# bqZUM_Bluetooth.net
KiCad netlist of a schematic drawn in Altium Designer
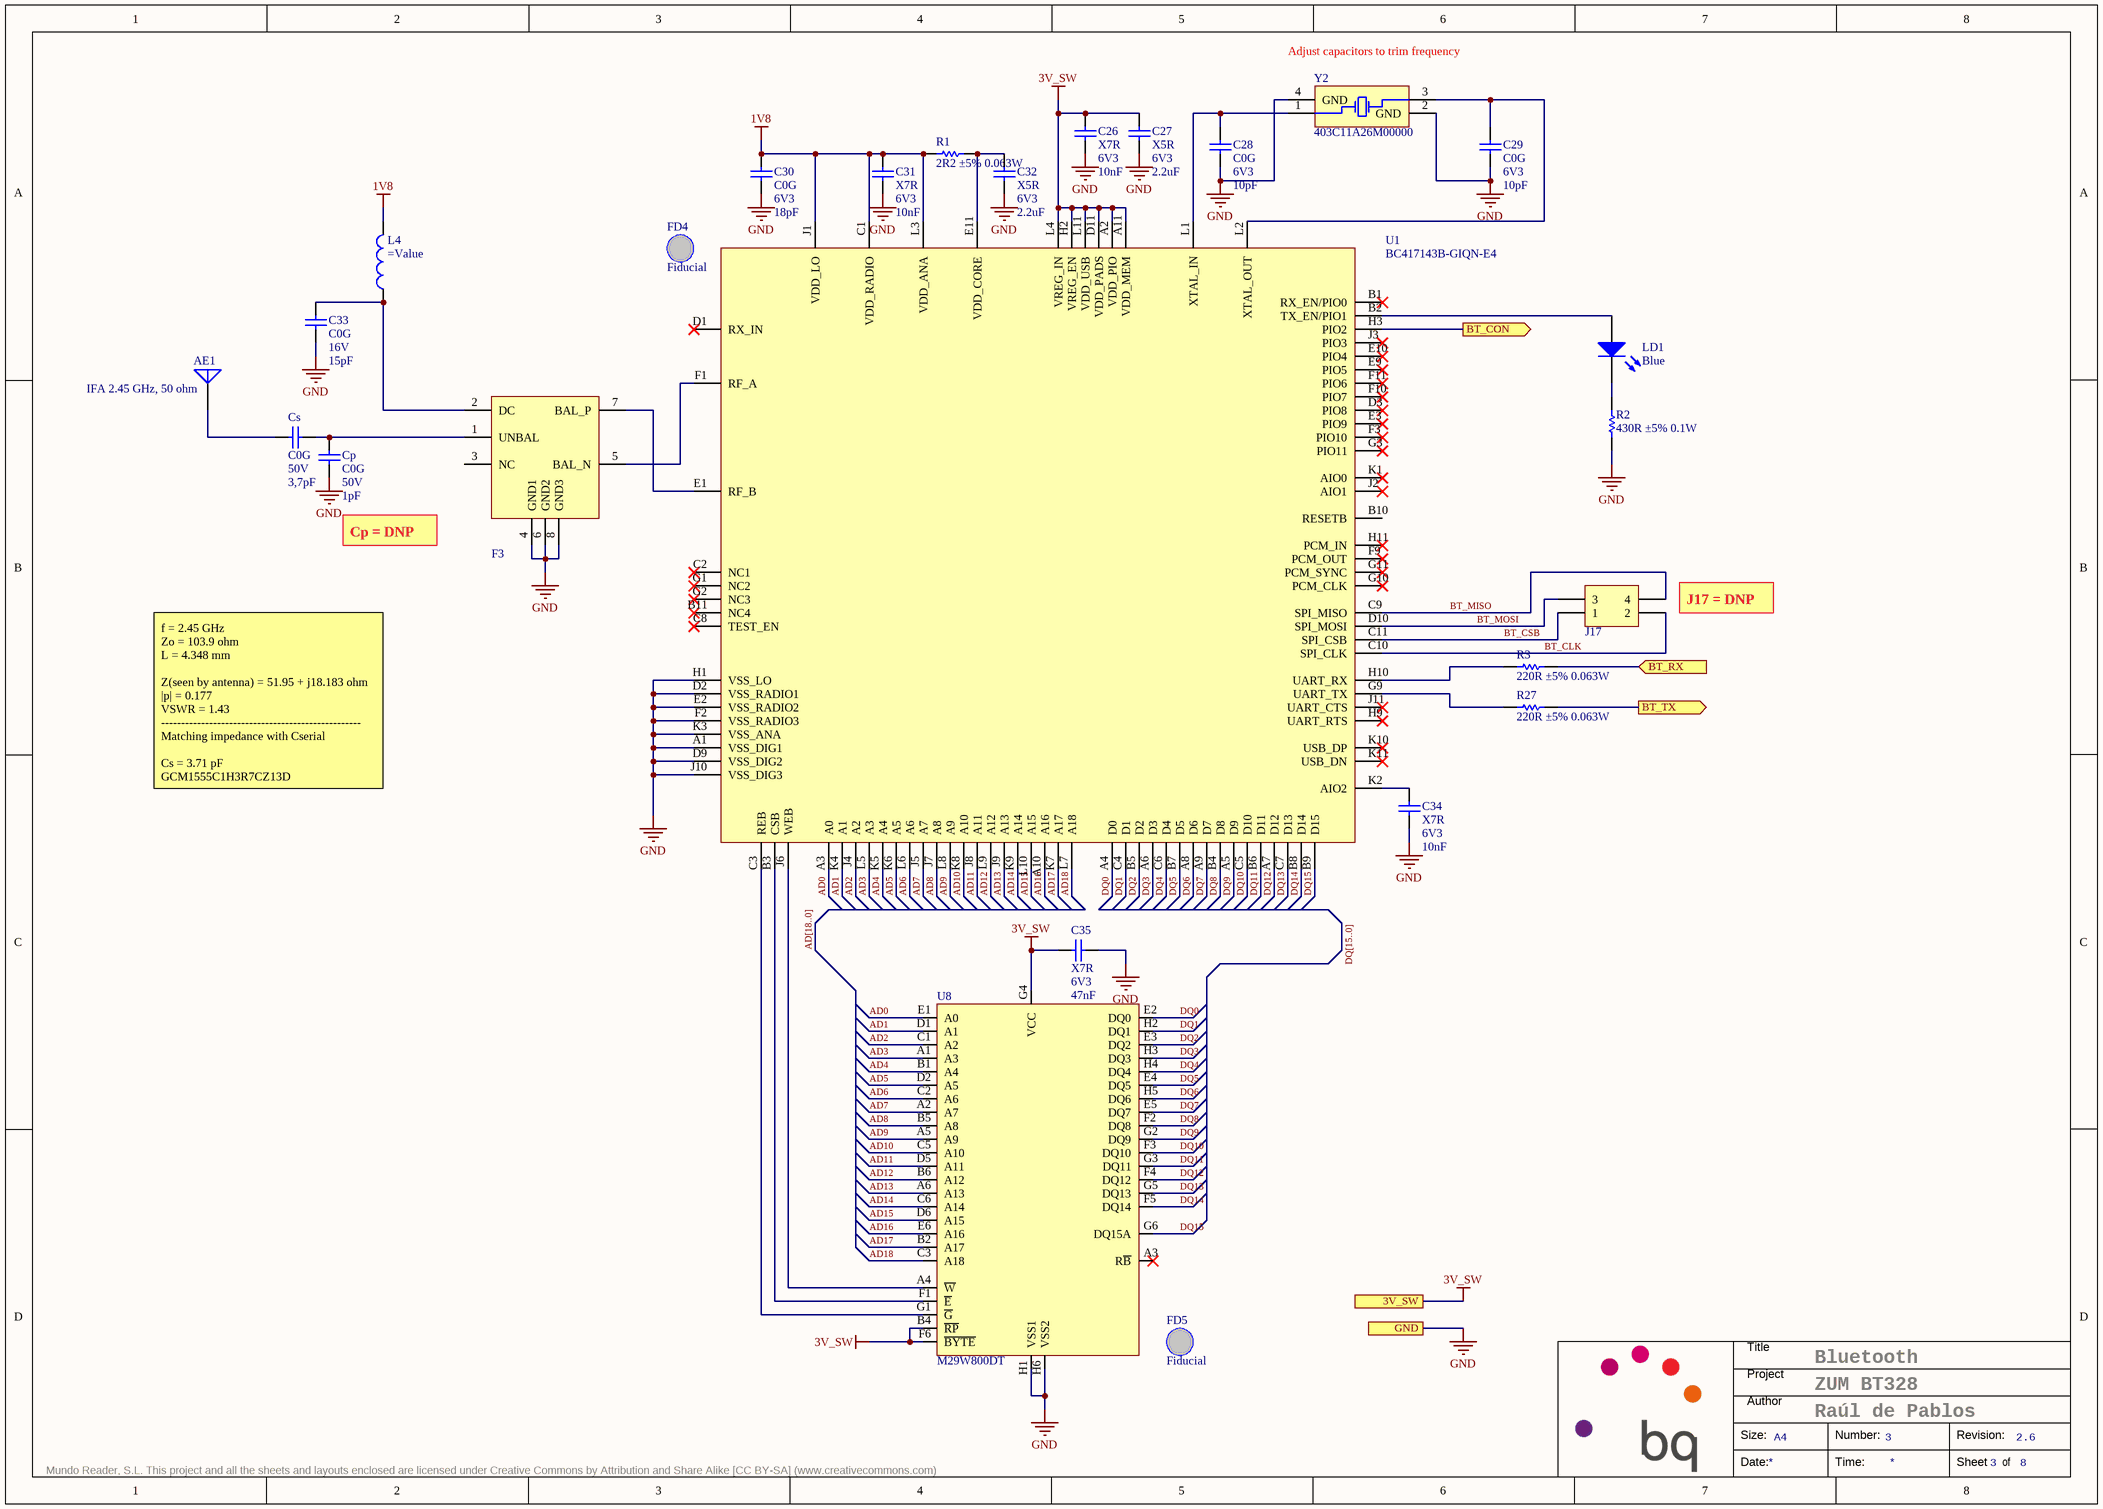
[diagram p0: bqZUM_Bluetooth.SchDoc]

(export (version "E")
  (design (tool "Eeschema 10.0.6"))
  (components
    (comp (ref "AE1")
      (value "~")
      (footprint "IFA_2,45GHZ_50OHM")
      (description "Antenna with Ground")
      (fields (field (name "PART NUMBER") "Microstrip_2.4GHz"))
      (libsource (lib "Connectors_Antenna") (part "Antenna_WG"))
    )
    (comp (ref "C26")
      (value "Capacitor")
      (footprint "C0402")
      (fields
        (field (name "DIELECTRIC") "X7R")
        (field (name "VOLTAGE") "6V3")
        (field (name "CAPACITANCE") "10nF")
        (field (name "PART NUMBER") "C0402_10nF_6V3_±10%")
        (field (name "TOLERANCE") "±10%")
        (field (name "MANUFACTURER") "Kemet")
      )
      (libsource (lib "Pasives_Capacitor_SMD") (part "Capacitor"))
    )
    (comp (ref "C27")
      (value "Capacitor")
      (footprint "C0603")
      (fields
        (field (name "DIELECTRIC") "X5R")
        (field (name "VOLTAGE") "6V3")
        (field (name "CAPACITANCE") "2.2uF")
        (field (name "PART NUMBER") "C0603_2.2uF_6V3_±10%")
        (field (name "TOLERANCE") "±10%")
        (field (name "MANUFACTURER") "Kemet")
      )
      (libsource (lib "Pasives_Capacitor_SMD") (part "Capacitor"))
    )
    (comp (ref "C28")
      (value "Capacitor")
      (footprint "C0402")
      (fields
        (field (name "DIELECTRIC") "C0G")
        (field (name "VOLTAGE") "6V3")
        (field (name "CAPACITANCE") "10pF")
        (field (name "PART NUMBER") "C0402_10pF_6V3_±10%")
        (field (name "TOLERANCE") "±10%")
        (field (name "MANUFACTURER") "Kemet")
      )
      (libsource (lib "Pasives_Capacitor_SMD") (part "Capacitor"))
    )
    (comp (ref "C29")
      (value "Capacitor")
      (footprint "C0402")
      (fields
        (field (name "DIELECTRIC") "C0G")
        (field (name "VOLTAGE") "6V3")
        (field (name "CAPACITANCE") "10pF")
        (field (name "PART NUMBER") "C0402_10pF_6V3_±10%")
        (field (name "TOLERANCE") "±10%")
        (field (name "MANUFACTURER") "Kemet")
      )
      (libsource (lib "Pasives_Capacitor_SMD") (part "Capacitor"))
    )
    (comp (ref "C30")
      (value "Capacitor")
      (footprint "C0402")
      (fields
        (field (name "DIELECTRIC") "C0G")
        (field (name "VOLTAGE") "6V3")
        (field (name "CAPACITANCE") "18pF")
        (field (name "PART NUMBER") "C0402_18pF_6V3_±10%")
        (field (name "TOLERANCE") "±10%")
        (field (name "MANUFACTURER") "Kemet")
      )
      (libsource (lib "Pasives_Capacitor_SMD") (part "Capacitor"))
    )
    (comp (ref "C31")
      (value "Capacitor")
      (footprint "C0402")
      (fields
        (field (name "DIELECTRIC") "X7R")
        (field (name "VOLTAGE") "6V3")
        (field (name "CAPACITANCE") "10nF")
        (field (name "PART NUMBER") "C0402_10nF_6V3_±10%")
        (field (name "TOLERANCE") "±10%")
        (field (name "MANUFACTURER") "Kemet")
      )
      (libsource (lib "Pasives_Capacitor_SMD") (part "Capacitor"))
    )
    (comp (ref "C32")
      (value "Capacitor")
      (footprint "C0603")
      (fields
        (field (name "DIELECTRIC") "X5R")
        (field (name "VOLTAGE") "6V3")
        (field (name "CAPACITANCE") "2.2uF")
        (field (name "PART NUMBER") "C0603_2.2uF_6V3_±10%")
        (field (name "TOLERANCE") "±10%")
        (field (name "MANUFACTURER") "Kemet")
      )
      (libsource (lib "Pasives_Capacitor_SMD") (part "Capacitor"))
    )
    (comp (ref "C33")
      (value "Capacitor")
      (footprint "C0402")
      (fields
        (field (name "DIELECTRIC") "C0G")
        (field (name "VOLTAGE") "16V")
        (field (name "CAPACITANCE") "15pF")
        (field (name "PART NUMBER") "C0402_15pF_16V_±10%")
        (field (name "TOLERANCE") "±10%")
        (field (name "MANUFACTURER") "Kemet")
      )
      (libsource (lib "Pasives_Capacitor_SMD") (part "Capacitor"))
    )
    (comp (ref "C34")
      (value "Capacitor")
      (footprint "C0402")
      (fields
        (field (name "DIELECTRIC") "X7R")
        (field (name "VOLTAGE") "6V3")
        (field (name "CAPACITANCE") "10nF")
        (field (name "PART NUMBER") "C0402_10nF_6V3_±10%")
        (field (name "TOLERANCE") "±10%")
        (field (name "MANUFACTURER") "Kemet")
      )
      (libsource (lib "Pasives_Capacitor_SMD") (part "Capacitor"))
    )
    (comp (ref "C35")
      (value "Capacitor")
      (footprint "C0402")
      (fields
        (field (name "DIELECTRIC") "X7R")
        (field (name "VOLTAGE") "6V3")
        (field (name "CAPACITANCE") "47nF")
        (field (name "PART NUMBER") "C0402_47nF_6V3_±10%")
        (field (name "TOLERANCE") "±10%")
        (field (name "MANUFACTURER") "Kemet")
      )
      (libsource (lib "Pasives_Capacitor_SMD") (part "Capacitor"))
    )
    (comp (ref "Cp")
      (value "Capacitor")
      (footprint "C0402")
      (fields
        (field (name "DIELECTRIC") "C0G")
        (field (name "VOLTAGE") "50V")
        (field (name "CAPACITANCE") "1pF")
        (field (name "PART NUMBER") "C0402_1pF_50V_0.25pF")
        (field (name "TOLERANCE") "0.25pF")
        (field (name "MANUFACTURER") "Murata")
      )
      (libsource (lib "Pasives_Capacitor_SMD") (part "Capacitor"))
    )
    (comp (ref "Cs")
      (value "Capacitor")
      (footprint "C0402")
      (fields
        (field (name "DIELECTRIC") "C0G")
        (field (name "VOLTAGE") "50V")
        (field (name "CAPACITANCE") "3,7pF")
        (field (name "PART NUMBER") "C0402_3,7pF_50V_±7%")
        (field (name "TOLERANCE") "±7%")
        (field (name "MANUFACTURER") "Murata")
      )
      (libsource (lib "Pasives_Capacitor_SMD") (part "Capacitor"))
    )
    (comp (ref "F3")
      (value "BP_Filter_Balun")
      (footprint "2450FB15K0005")
      (description "Band Pass Balun Filter")
      (fields (field (name "MANUFACTURER") "Johanson Technlogy"))
      (libsource (lib "Pasives_Filter") (part "BP_Filter_Balun"))
    )
    (comp (ref "FD4")
      (value "Fiducial")
      (footprint "Fiducial_Local_0.4mm")
      (fields (field (name "PART NUMBER") "Fiducial Local 0.4mm"))
      (libsource (lib "Miscelanea") (part "Fiducial"))
    )
    (comp (ref "FD5")
      (value "Fiducial")
      (footprint "Fiducial_Local_0.4mm")
      (fields (field (name "PART NUMBER") "Fiducial Local 0.4mm"))
      (libsource (lib "Miscelanea") (part "Fiducial"))
    )
    (comp (ref "J17")
      (value "2x2 Header 1.27mm")
      (footprint "2x2 Header THT 1.27mm")
      (description "4 pin Dual Header 1.27mm")
      (fields (field (name "MANUFACTURER") "Würth") (field (name "PART NUMBER") "CON_DPH_THT_1.27_4"))
      (libsource (lib "Conectores_PinHeader_1.27") (part "2x2 Header 1.27mm"))
    )
    (comp (ref "L4")
      (value "~")
      (footprint "L0402")
      (description "Inductor SMD")
      (fields (field (name "PART NUMBER") "15nH_0,3A") (field (name "MANUFACTURER") "Murata"))
      (libsource (lib "Pasivos_Inductor_SMD") (part "Inductor"))
    )
    (comp (ref "LD1")
      (value "Blue")
      (footprint "LED0603")
      (description "Light Emitting Diode")
      (fields (field (name "PART NUMBER") "LTST-C194TBKT") (field (name "MANUFACTURER") "Lite-On"))
      (libsource (lib "Optoelectronics") (part "LED"))
    )
    (comp (ref "R1")
      (value "2R2 ±5% 0.063W")
      (footprint "R0402")
      (description "Resistor")
      (fields (field (name "TOLERANCE") "±5%") (field (name "POWER") "0.063W"))
      (libsource (lib "Pasives_Resistor_SMD") (part "Resistor"))
    )
    (comp (ref "R2")
      (value "430R ±5% 0.1W")
      (footprint "R0603")
      (description "Resistor")
      (fields (field (name "TOLERANCE") "±5%") (field (name "POWER") "0.1W"))
      (libsource (lib "Pasives_Resistor_SMD") (part "Resistor"))
    )
    (comp (ref "R3")
      (value "220R ±5% 0.063W")
      (footprint "R0402")
      (description "Resistor")
      (fields (field (name "TOLERANCE") "±5%") (field (name "POWER") "0.063W"))
      (libsource (lib "Pasives_Resistor_SMD") (part "Resistor"))
    )
    (comp (ref "R27")
      (value "220R ±5% 0.063W")
      (footprint "R0402")
      (description "Resistor")
      (fields (field (name "TOLERANCE") "±5%") (field (name "POWER") "0.063W"))
      (libsource (lib "Pasives_Resistor_SMD") (part "Resistor"))
    )
    (comp (ref "U1")
      (value "BC417143B-GIQN-E4")
      (footprint "TFBGA96P8X8")
      (description "Bluetooth Modem, 2.4-GHz Bluetooth SoC")
      (fields (field (name "PART NUMBER") "BlueCore4-EXT") (field (name "MANUFACTURER") "CSR"))
      (libsource (lib "Transceiver") (part "BC417143B"))
    )
    (comp (ref "U8")
      (value "S29AL008J70BFI02")
      (footprint "TFBGA48P6X8")
      (description "Memory NOR Flash 8-Mbit 3 V supply")
      (fields (field (name "PART NUMBER") "M29W800DT") (field (name "MANUFACTURER") "Spansion"))
      (libsource (lib "Memory_NOR") (part "M29W800DT"))
    )
    (comp (ref "Y2")
      (value "403C11A26M00000")
      (footprint "XTAL 3.2x2.5")
      (description "Crystal")
      (fields (field (name "PART NUMBER") "403C11A 26MHz") (field (name "TOLERANCE") "±10ppm"))
      (libsource (lib "Frequency") (part "Crystal 4 pin"))
    )
  )
  (nets
    (net (code "1") (name "/AD0") (class "Default")
      (node (ref "U1") (pin "A3") (pinfunction "A0_A3") (pintype "passive"))
      (node (ref "U8") (pin "E1") (pinfunction "A0_E1") (pintype "passive"))
    )
    (net (code "2") (name "/AD1") (class "Default")
      (node (ref "U1") (pin "K4") (pinfunction "A1_K4") (pintype "passive"))
      (node (ref "U8") (pin "D1") (pinfunction "A1_D1") (pintype "passive"))
    )
    (net (code "3") (name "/AD2") (class "Default")
      (node (ref "U1") (pin "J4") (pinfunction "A2_J4") (pintype "passive"))
      (node (ref "U8") (pin "C1") (pinfunction "A2_C1") (pintype "passive"))
    )
    (net (code "4") (name "/AD3") (class "Default")
      (node (ref "U1") (pin "L5") (pinfunction "A3_L5") (pintype "passive"))
      (node (ref "U8") (pin "A1") (pinfunction "A3_A1") (pintype "passive"))
    )
    (net (code "5") (name "/AD4") (class "Default")
      (node (ref "U1") (pin "K5") (pinfunction "A4_K5") (pintype "passive"))
      (node (ref "U8") (pin "B1") (pinfunction "A4_B1") (pintype "passive"))
    )
    (net (code "6") (name "/AD5") (class "Default")
      (node (ref "U1") (pin "K6") (pinfunction "A5_K6") (pintype "passive"))
      (node (ref "U8") (pin "D2") (pinfunction "A5_D2") (pintype "passive"))
    )
    (net (code "7") (name "/AD6") (class "Default")
      (node (ref "U1") (pin "L6") (pinfunction "A6_L6") (pintype "passive"))
      (node (ref "U8") (pin "C2") (pinfunction "A6_C2") (pintype "passive"))
    )
    (net (code "8") (name "/AD7") (class "Default")
      (node (ref "U1") (pin "J5") (pinfunction "A7_J5") (pintype "passive"))
      (node (ref "U8") (pin "A2") (pinfunction "A7_A2") (pintype "passive"))
    )
    (net (code "9") (name "/AD8") (class "Default")
      (node (ref "U1") (pin "J7") (pinfunction "A8_J7") (pintype "passive"))
      (node (ref "U8") (pin "B5") (pinfunction "A8_B5") (pintype "passive"))
    )
    (net (code "10") (name "/AD9") (class "Default")
      (node (ref "U1") (pin "L8") (pinfunction "A9_L8") (pintype "passive"))
      (node (ref "U8") (pin "A5") (pinfunction "A9_A5") (pintype "passive"))
    )
    (net (code "11") (name "/AD10") (class "Default")
      (node (ref "U1") (pin "K8") (pinfunction "A10_K8") (pintype "passive"))
      (node (ref "U8") (pin "C5") (pinfunction "A10_C5") (pintype "passive"))
    )
    (net (code "12") (name "/AD11") (class "Default")
      (node (ref "U1") (pin "J8") (pinfunction "A11_J8") (pintype "passive"))
      (node (ref "U8") (pin "D5") (pinfunction "A11_D5") (pintype "passive"))
    )
    (net (code "13") (name "/AD12") (class "Default")
      (node (ref "U1") (pin "L9") (pinfunction "A12_L9") (pintype "passive"))
      (node (ref "U8") (pin "B6") (pinfunction "A12_B6") (pintype "passive"))
    )
    (net (code "14") (name "/AD13") (class "Default")
      (node (ref "U1") (pin "J9") (pinfunction "A13_J9") (pintype "passive"))
      (node (ref "U8") (pin "A6") (pinfunction "A13_A6") (pintype "passive"))
    )
    (net (code "15") (name "/AD14") (class "Default")
      (node (ref "U1") (pin "K9") (pinfunction "A14_K9") (pintype "passive"))
      (node (ref "U8") (pin "C6") (pinfunction "A14_C6") (pintype "passive"))
    )
    (net (code "16") (name "/AD15") (class "Default")
      (node (ref "U1") (pin "L10") (pinfunction "A15_L10") (pintype "passive"))
      (node (ref "U8") (pin "D6") (pinfunction "A15_D6") (pintype "passive"))
    )
    (net (code "17") (name "/AD16") (class "Default")
      (node (ref "U1") (pin "A10") (pinfunction "A16_A10") (pintype "passive"))
      (node (ref "U8") (pin "E6") (pinfunction "A16_E6") (pintype "passive"))
    )
    (net (code "18") (name "/AD17") (class "Default")
      (node (ref "U1") (pin "K7") (pinfunction "A17_K7") (pintype "passive"))
      (node (ref "U8") (pin "B2") (pinfunction "A17_B2") (pintype "passive"))
    )
    (net (code "19") (name "/AD18") (class "Default")
      (node (ref "U1") (pin "L7") (pinfunction "A18_L7") (pintype "passive"))
      (node (ref "U8") (pin "C3") (pinfunction "A18_C3") (pintype "passive"))
    )
    (net (code "21") (name "/BT_CLK") (class "Default")
      (node (ref "J17") (pin "2") (pinfunction "2_2") (pintype "passive"))
      (node (ref "U1") (pin "C10") (pinfunction "SPI_CLK_C10") (pintype "passive"))
    )
    (net (code "22") (name "/BT_CON") (class "Default")
      (node (ref "U1") (pin "H3") (pinfunction "PIO2_H3") (pintype "passive"))
    )
    (net (code "23") (name "/BT_CSB") (class "Default")
      (node (ref "J17") (pin "1") (pinfunction "1_1") (pintype "passive"))
      (node (ref "U1") (pin "C11") (pinfunction "SPI_CSB_C11") (pintype "passive"))
    )
    (net (code "24") (name "/BT_MISO") (class "Default")
      (node (ref "J17") (pin "4") (pinfunction "4_4") (pintype "passive"))
      (node (ref "U1") (pin "C9") (pinfunction "SPI_MISO_C9") (pintype "passive"))
    )
    (net (code "25") (name "/BT_MOSI") (class "Default")
      (node (ref "J17") (pin "3") (pinfunction "3_3") (pintype "passive"))
      (node (ref "U1") (pin "D10") (pinfunction "SPI_MOSI_D10") (pintype "passive"))
    )
    (net (code "26") (name "/BT_RX") (class "Default")
      (node (ref "R3") (pin "2") (pinfunction "2_2") (pintype "passive"))
    )
    (net (code "27") (name "/BT_TX") (class "Default")
      (node (ref "R27") (pin "2") (pinfunction "2_2") (pintype "passive"))
    )
    (net (code "28") (name "/DQ0") (class "Default")
      (node (ref "U1") (pin "A4") (pinfunction "D0_A4") (pintype "passive"))
      (node (ref "U8") (pin "E2") (pinfunction "DQ0_E2") (pintype "passive"))
    )
    (net (code "29") (name "/DQ1") (class "Default")
      (node (ref "U1") (pin "C4") (pinfunction "D1_C4") (pintype "passive"))
      (node (ref "U8") (pin "H2") (pinfunction "DQ1_H2") (pintype "passive"))
    )
    (net (code "30") (name "/DQ2") (class "Default")
      (node (ref "U1") (pin "B5") (pinfunction "D2_B5") (pintype "passive"))
      (node (ref "U8") (pin "E3") (pinfunction "DQ2_E3") (pintype "passive"))
    )
    (net (code "31") (name "/DQ3") (class "Default")
      (node (ref "U1") (pin "A6") (pinfunction "D3_A6") (pintype "passive"))
      (node (ref "U8") (pin "H3") (pinfunction "DQ3_H3") (pintype "passive"))
    )
    (net (code "32") (name "/DQ4") (class "Default")
      (node (ref "U1") (pin "C6") (pinfunction "D4_C6") (pintype "passive"))
      (node (ref "U8") (pin "H4") (pinfunction "DQ4_H4") (pintype "passive"))
    )
    (net (code "33") (name "/DQ5") (class "Default")
      (node (ref "U1") (pin "B7") (pinfunction "D5_B7") (pintype "passive"))
      (node (ref "U8") (pin "E4") (pinfunction "DQ5_E4") (pintype "passive"))
    )
    (net (code "34") (name "/DQ6") (class "Default")
      (node (ref "U1") (pin "A8") (pinfunction "D6_A8") (pintype "passive"))
      (node (ref "U8") (pin "H5") (pinfunction "DQ6_H5") (pintype "passive"))
    )
    (net (code "35") (name "/DQ7") (class "Default")
      (node (ref "U1") (pin "A9") (pinfunction "D7_A9") (pintype "passive"))
      (node (ref "U8") (pin "E5") (pinfunction "DQ7_E5") (pintype "passive"))
    )
    (net (code "36") (name "/DQ8") (class "Default")
      (node (ref "U1") (pin "B4") (pinfunction "D8_B4") (pintype "passive"))
      (node (ref "U8") (pin "F2") (pinfunction "DQ8_F2") (pintype "passive"))
    )
    (net (code "37") (name "/DQ9") (class "Default")
      (node (ref "U1") (pin "A5") (pinfunction "D9_A5") (pintype "passive"))
      (node (ref "U8") (pin "G2") (pinfunction "DQ9_G2") (pintype "passive"))
    )
    (net (code "38") (name "/DQ10") (class "Default")
      (node (ref "U1") (pin "C5") (pinfunction "D10_C5") (pintype "passive"))
      (node (ref "U8") (pin "F3") (pinfunction "DQ10_F3") (pintype "passive"))
    )
    (net (code "39") (name "/DQ11") (class "Default")
      (node (ref "U1") (pin "B6") (pinfunction "D11_B6") (pintype "passive"))
      (node (ref "U8") (pin "G3") (pinfunction "DQ11_G3") (pintype "passive"))
    )
    (net (code "40") (name "/DQ12") (class "Default")
      (node (ref "U1") (pin "A7") (pinfunction "D12_A7") (pintype "passive"))
      (node (ref "U8") (pin "F4") (pinfunction "DQ12_F4") (pintype "passive"))
    )
    (net (code "41") (name "/DQ13") (class "Default")
      (node (ref "U1") (pin "C7") (pinfunction "D13_C7") (pintype "passive"))
      (node (ref "U8") (pin "G5") (pinfunction "DQ13_G5") (pintype "passive"))
    )
    (net (code "42") (name "/DQ14") (class "Default")
      (node (ref "U1") (pin "B8") (pinfunction "D14_B8") (pintype "passive"))
      (node (ref "U8") (pin "F5") (pinfunction "DQ14_F5") (pintype "passive"))
    )
    (net (code "43") (name "/DQ15") (class "Default")
      (node (ref "U1") (pin "B9") (pinfunction "D15_B9") (pintype "passive"))
      (node (ref "U8") (pin "G6") (pinfunction "DQ15A_G6") (pintype "passive"))
    )
    (net (code "45") (name "1V8") (class "Default")
      (node (ref "C30") (pin "2") (pinfunction "2_2") (pintype "passive"))
      (node (ref "C31") (pin "2") (pinfunction "2_2") (pintype "passive"))
      (node (ref "L4") (pin "2") (pinfunction "2_2") (pintype "passive"))
      (node (ref "R1") (pin "2") (pinfunction "2_2") (pintype "passive"))
      (node (ref "U1") (pin "C1") (pinfunction "VDD_RADIO_C1") (pintype "passive"))
      (node (ref "U1") (pin "J1") (pinfunction "VDD_LO_J1") (pintype "passive"))
      (node (ref "U1") (pin "L3") (pinfunction "VDD_ANA_L3") (pintype "passive"))
    )
    (net (code "46") (name "3V_SW") (class "Default")
      (node (ref "C26") (pin "2") (pinfunction "2_2") (pintype "passive"))
      (node (ref "C27") (pin "2") (pinfunction "2_2") (pintype "passive"))
      (node (ref "C35") (pin "1") (pinfunction "1_1") (pintype "passive"))
      (node (ref "U1") (pin "A11") (pinfunction "VDD_MEM_A11") (pintype "passive"))
      (node (ref "U1") (pin "A2") (pinfunction "VDD_PIO_A2") (pintype "passive"))
      (node (ref "U1") (pin "D11") (pinfunction "VDD_PADS_D11") (pintype "passive"))
      (node (ref "U1") (pin "H2") (pinfunction "VREG_EN_H2") (pintype "passive"))
      (node (ref "U1") (pin "L11") (pinfunction "VDD_USB_L11") (pintype "passive"))
      (node (ref "U1") (pin "L4") (pinfunction "VREG_IN_L4") (pintype "passive"))
      (node (ref "U8") (pin "B4") (pinfunction "~{RP}_B4") (pintype "passive"))
      (node (ref "U8") (pin "F6") (pinfunction "~{BYTE}_F6") (pintype "passive"))
      (node (ref "U8") (pin "G4") (pinfunction "VCC_G4") (pintype "passive"))
    )
    (net (code "47") (name "GND") (class "Default")
      (node (ref "C26") (pin "1") (pinfunction "1_1") (pintype "passive"))
      (node (ref "C27") (pin "1") (pinfunction "1_1") (pintype "passive"))
      (node (ref "C28") (pin "1") (pinfunction "1_1") (pintype "passive"))
      (node (ref "C29") (pin "1") (pinfunction "1_1") (pintype "passive"))
      (node (ref "C30") (pin "1") (pinfunction "1_1") (pintype "passive"))
      (node (ref "C31") (pin "1") (pinfunction "1_1") (pintype "passive"))
      (node (ref "C32") (pin "1") (pinfunction "1_1") (pintype "passive"))
      (node (ref "C33") (pin "1") (pinfunction "1_1") (pintype "passive"))
      (node (ref "C34") (pin "1") (pinfunction "1_1") (pintype "passive"))
      (node (ref "C35") (pin "2") (pinfunction "2_2") (pintype "passive"))
      (node (ref "Cp") (pin "1") (pinfunction "1_1") (pintype "passive"))
      (node (ref "F3") (pin "4") (pinfunction "GND1_4") (pintype "power_in"))
      (node (ref "F3") (pin "6") (pinfunction "GND2_6") (pintype "power_in"))
      (node (ref "F3") (pin "8") (pinfunction "GND3_8") (pintype "power_in"))
      (node (ref "R2") (pin "1") (pinfunction "1_1") (pintype "passive"))
      (node (ref "U1") (pin "A1") (pinfunction "VSS_DIG1_A1") (pintype "passive"))
      (node (ref "U1") (pin "D2") (pinfunction "VSS_RADIO1_D2") (pintype "passive"))
      (node (ref "U1") (pin "D9") (pinfunction "VSS_DIG2_D9") (pintype "passive"))
      (node (ref "U1") (pin "E2") (pinfunction "VSS_RADIO2_E2") (pintype "passive"))
      (node (ref "U1") (pin "F2") (pinfunction "VSS_RADIO3_F2") (pintype "passive"))
      (node (ref "U1") (pin "H1") (pinfunction "VSS_LO_H1") (pintype "passive"))
      (node (ref "U1") (pin "J10") (pinfunction "VSS_DIG3_J10") (pintype "passive"))
      (node (ref "U1") (pin "K3") (pinfunction "VSS_ANA_K3") (pintype "passive"))
      (node (ref "U8") (pin "H1") (pinfunction "VSS1_H1") (pintype "passive"))
      (node (ref "U8") (pin "H6") (pinfunction "VSS2_H6") (pintype "passive"))
      (node (ref "Y2") (pin "2") (pinfunction "GND_2") (pintype "passive"))
      (node (ref "Y2") (pin "4") (pinfunction "GND_4") (pintype "passive"))
    )
    (net (code "48") (name "Net-(AE1-PadFEED)") (class "Default")
      (node (ref "AE1") (pin "FEED") (pinfunction "FEED_FEED") (pintype "passive"))
      (node (ref "Cs") (pin "1") (pinfunction "1_1") (pintype "passive"))
    )
    (net (code "49") (name "Net-(F3-BAL_N)") (class "Default")
      (node (ref "F3") (pin "5") (pinfunction "BAL_N_5") (pintype "passive"))
      (node (ref "U1") (pin "F1") (pinfunction "RF_A_F1") (pintype "passive"))
    )
    (net (code "50") (name "Net-(F3-BAL_P)") (class "Default")
      (node (ref "F3") (pin "7") (pinfunction "BAL_P_7") (pintype "passive"))
      (node (ref "U1") (pin "E1") (pinfunction "RF_B_E1") (pintype "passive"))
    )
    (net (code "51") (name "Net-(F3-DC)") (class "Default")
      (node (ref "C33") (pin "2") (pinfunction "2_2") (pintype "passive"))
      (node (ref "F3") (pin "2") (pinfunction "DC_2") (pintype "passive"))
      (node (ref "L4") (pin "1") (pinfunction "1_1") (pintype "passive"))
    )
    (net (code "52") (name "Net-(F3-UNBAL)") (class "Default")
      (node (ref "Cp") (pin "2") (pinfunction "2_2") (pintype "passive"))
      (node (ref "Cs") (pin "2") (pinfunction "2_2") (pintype "passive"))
      (node (ref "F3") (pin "1") (pinfunction "UNBAL_1") (pintype "passive"))
    )
    (net (code "53") (name "Net-(LD1-PadK)") (class "Default")
      (node (ref "LD1") (pin "K") (pinfunction "K_K") (pintype "passive"))
      (node (ref "R2") (pin "2") (pinfunction "2_2") (pintype "passive"))
    )
    (net (code "54") (name "Net-(U1-AIO2)") (class "Default")
      (node (ref "C34") (pin "2") (pinfunction "2_2") (pintype "passive"))
      (node (ref "U1") (pin "K2") (pinfunction "AIO2_K2") (pintype "passive"))
    )
    (net (code "55") (name "Net-(U1-CSB)") (class "Default")
      (node (ref "U1") (pin "B3") (pinfunction "CSB_B3") (pintype "passive"))
      (node (ref "U8") (pin "F1") (pinfunction "~{E}_F1") (pintype "passive"))
    )
    (net (code "56") (name "Net-(U1-REB)") (class "Default")
      (node (ref "U1") (pin "C3") (pinfunction "REB_C3") (pintype "passive"))
      (node (ref "U8") (pin "G1") (pinfunction "~{G}_G1") (pintype "passive"))
    )
    (net (code "57") (name "Net-(U1-TX_EN{slash}PIO1)") (class "Default")
      (node (ref "LD1") (pin "A") (pinfunction "A_A") (pintype "passive"))
      (node (ref "U1") (pin "B2") (pinfunction "TX_EN/PIO1_B2") (pintype "passive"))
    )
    (net (code "58") (name "Net-(U1-UART_RX)") (class "Default")
      (node (ref "R3") (pin "1") (pinfunction "1_1") (pintype "passive"))
      (node (ref "U1") (pin "H10") (pinfunction "UART_RX_H10") (pintype "passive"))
    )
    (net (code "59") (name "Net-(U1-UART_TX)") (class "Default")
      (node (ref "R27") (pin "1") (pinfunction "1_1") (pintype "passive"))
      (node (ref "U1") (pin "G9") (pinfunction "UART_TX_G9") (pintype "passive"))
    )
    (net (code "60") (name "Net-(U1-VDD_CORE)") (class "Default")
      (node (ref "C32") (pin "2") (pinfunction "2_2") (pintype "passive"))
      (node (ref "R1") (pin "1") (pinfunction "1_1") (pintype "passive"))
      (node (ref "U1") (pin "E11") (pinfunction "VDD_CORE_E11") (pintype "passive"))
    )
    (net (code "61") (name "Net-(U1-WEB)") (class "Default")
      (node (ref "U1") (pin "J6") (pinfunction "WEB_J6") (pintype "passive"))
      (node (ref "U8") (pin "A4") (pinfunction "~{W}_A4") (pintype "passive"))
    )
    (net (code "62") (name "Net-(U1-XTAL_IN)") (class "Default")
      (node (ref "C28") (pin "2") (pinfunction "2_2") (pintype "passive"))
      (node (ref "U1") (pin "L1") (pinfunction "XTAL_IN_L1") (pintype "passive"))
      (node (ref "Y2") (pin "1") (pinfunction "OSC1_1") (pintype "passive"))
    )
    (net (code "63") (name "Net-(U1-XTAL_OUT)") (class "Default")
      (node (ref "C29") (pin "2") (pinfunction "2_2") (pintype "passive"))
      (node (ref "U1") (pin "L2") (pinfunction "XTAL_OUT_L2") (pintype "passive"))
      (node (ref "Y2") (pin "3") (pinfunction "OSC2_3") (pintype "passive"))
    )
    (net (code "64") (name "unconnected-(AE1-PadGND)") (class "Default")
      (node (ref "AE1") (pin "GND") (pinfunction "GND_GND") (pintype "passive"))
    )
    (net (code "65") (name "unconnected-(F3-NC-Pad3)") (class "Default")
      (node (ref "F3") (pin "3") (pinfunction "NC_3") (pintype "passive"))
    )
    (net (code "66") (name "unconnected-(U1-AIO0-PadK1)") (class "Default")
      (node (ref "U1") (pin "K1") (pinfunction "AIO0_K1") (pintype "passive+no_connect"))
    )
    (net (code "67") (name "unconnected-(U1-AIO1-PadJ2)") (class "Default")
      (node (ref "U1") (pin "J2") (pinfunction "AIO1_J2") (pintype "passive+no_connect"))
    )
    (net (code "68") (name "unconnected-(U1-NC1-PadC2)") (class "Default")
      (node (ref "U1") (pin "C2") (pinfunction "NC1_C2") (pintype "passive+no_connect"))
    )
    (net (code "69") (name "unconnected-(U1-NC2-PadG1)") (class "Default")
      (node (ref "U1") (pin "G1") (pinfunction "NC2_G1") (pintype "passive+no_connect"))
    )
    (net (code "70") (name "unconnected-(U1-NC3-PadG2)") (class "Default")
      (node (ref "U1") (pin "G2") (pinfunction "NC3_G2") (pintype "passive+no_connect"))
    )
    (net (code "71") (name "unconnected-(U1-NC4-PadB11)") (class "Default")
      (node (ref "U1") (pin "B11") (pinfunction "NC4_B11") (pintype "passive+no_connect"))
    )
    (net (code "72") (name "unconnected-(U1-PCM_CLK-PadG10)") (class "Default")
      (node (ref "U1") (pin "G10") (pinfunction "PCM_CLK_G10") (pintype "passive+no_connect"))
    )
    (net (code "73") (name "unconnected-(U1-PCM_IN-PadH11)") (class "Default")
      (node (ref "U1") (pin "H11") (pinfunction "PCM_IN_H11") (pintype "passive+no_connect"))
    )
    (net (code "74") (name "unconnected-(U1-PCM_OUT-PadF9)") (class "Default")
      (node (ref "U1") (pin "F9") (pinfunction "PCM_OUT_F9") (pintype "passive+no_connect"))
    )
    (net (code "75") (name "unconnected-(U1-PCM_SYNC-PadG11)") (class "Default")
      (node (ref "U1") (pin "G11") (pinfunction "PCM_SYNC_G11") (pintype "passive+no_connect"))
    )
    (net (code "76") (name "unconnected-(U1-PIO3-PadJ3)") (class "Default")
      (node (ref "U1") (pin "J3") (pinfunction "PIO3_J3") (pintype "passive+no_connect"))
    )
    (net (code "77") (name "unconnected-(U1-PIO4-PadE10)") (class "Default")
      (node (ref "U1") (pin "E10") (pinfunction "PIO4_E10") (pintype "passive+no_connect"))
    )
    (net (code "78") (name "unconnected-(U1-PIO5-PadE9)") (class "Default")
      (node (ref "U1") (pin "E9") (pinfunction "PIO5_E9") (pintype "passive+no_connect"))
    )
    (net (code "79") (name "unconnected-(U1-PIO6-PadF11)") (class "Default")
      (node (ref "U1") (pin "F11") (pinfunction "PIO6_F11") (pintype "passive+no_connect"))
    )
    (net (code "80") (name "unconnected-(U1-PIO7-PadF10)") (class "Default")
      (node (ref "U1") (pin "F10") (pinfunction "PIO7_F10") (pintype "passive+no_connect"))
    )
    (net (code "81") (name "unconnected-(U1-PIO8-PadD3)") (class "Default")
      (node (ref "U1") (pin "D3") (pinfunction "PIO8_D3") (pintype "passive+no_connect"))
    )
    (net (code "82") (name "unconnected-(U1-PIO9-PadE3)") (class "Default")
      (node (ref "U1") (pin "E3") (pinfunction "PIO9_E3") (pintype "passive+no_connect"))
    )
    (net (code "83") (name "unconnected-(U1-PIO10-PadF3)") (class "Default")
      (node (ref "U1") (pin "F3") (pinfunction "PIO10_F3") (pintype "passive+no_connect"))
    )
    (net (code "84") (name "unconnected-(U1-PIO11-PadG3)") (class "Default")
      (node (ref "U1") (pin "G3") (pinfunction "PIO11_G3") (pintype "passive+no_connect"))
    )
    (net (code "85") (name "unconnected-(U1-RESETB-PadB10)") (class "Default")
      (node (ref "U1") (pin "B10") (pinfunction "RESETB_B10") (pintype "passive"))
    )
    (net (code "86") (name "unconnected-(U1-RX_EN{slash}PIO0-PadB1)") (class "Default")
      (node (ref "U1") (pin "B1") (pinfunction "RX_EN/PIO0_B1") (pintype "passive+no_connect"))
    )
    (net (code "87") (name "unconnected-(U1-RX_IN-PadD1)") (class "Default")
      (node (ref "U1") (pin "D1") (pinfunction "RX_IN_D1") (pintype "passive+no_connect"))
    )
    (net (code "88") (name "unconnected-(U1-TEST_EN-PadC8)") (class "Default")
      (node (ref "U1") (pin "C8") (pinfunction "TEST_EN_C8") (pintype "passive+no_connect"))
    )
    (net (code "89") (name "unconnected-(U1-UART_CTS-PadJ11)") (class "Default")
      (node (ref "U1") (pin "J11") (pinfunction "UART_CTS_J11") (pintype "passive+no_connect"))
    )
    (net (code "90") (name "unconnected-(U1-UART_RTS-PadH9)") (class "Default")
      (node (ref "U1") (pin "H9") (pinfunction "UART_RTS_H9") (pintype "passive+no_connect"))
    )
    (net (code "91") (name "unconnected-(U1-USB_DN-PadK11)") (class "Default")
      (node (ref "U1") (pin "K11") (pinfunction "USB_DN_K11") (pintype "passive+no_connect"))
    )
    (net (code "92") (name "unconnected-(U1-USB_DP-PadK10)") (class "Default")
      (node (ref "U1") (pin "K10") (pinfunction "USB_DP_K10") (pintype "passive+no_connect"))
    )
    (net (code "93") (name "unconnected-(U8-R~{B}-PadA3)") (class "Default")
      (node (ref "U8") (pin "A3") (pinfunction "R~{B}_A3") (pintype "passive+no_connect"))
    )
  )
)
